# pre_amp.net
KiCad netlist of a schematic drawn in EAGLE
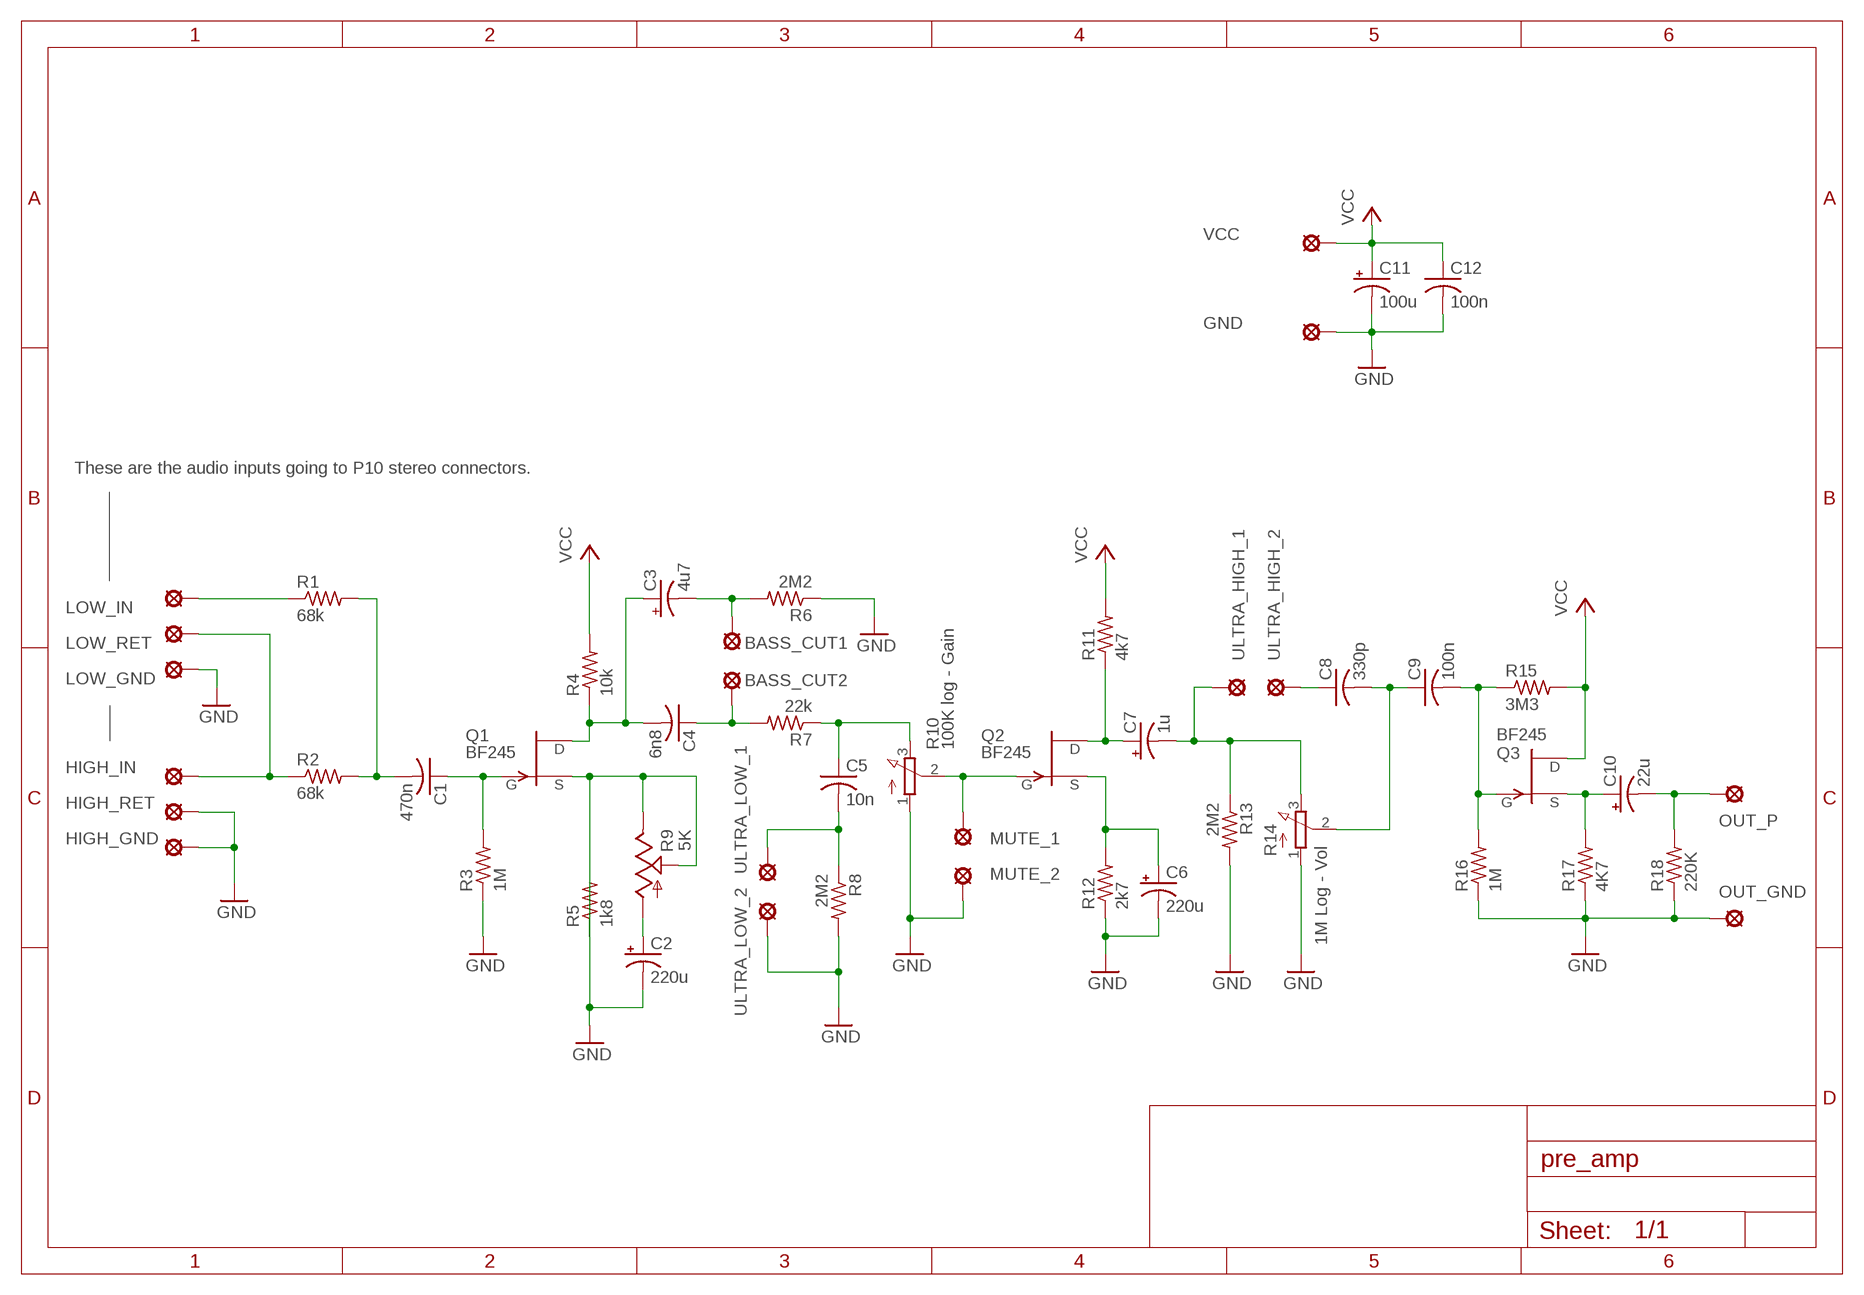
[diagram p0: schematic, sheet 1]

(export (version "E")
  (design (tool "Eeschema 10.0.6"))
  (components
    (comp (ref "BASS_CUT1")
      (value "MCS08")
      (footprint "eagle-import:MCS08")
      (libsource (lib "eagle-import") (part "MCS08"))
    )
    (comp (ref "BASS_CUT2")
      (value "MCS08")
      (footprint "eagle-import:MCS08")
      (libsource (lib "eagle-import") (part "MCS08"))
    )
    (comp (ref "C1")
      (value "470n")
      (footprint "eagle-import:C050-035X075")
      (libsource (lib "eagle-import") (part "resistor_C-US050-035X075"))
    )
    (comp (ref "C2")
      (value "220u")
      (footprint "eagle-import:E5-8,5")
      (libsource (lib "eagle-import") (part "resistor_CPOL-USE5-8.5"))
    )
    (comp (ref "C3")
      (value "4u7")
      (footprint "eagle-import:E2,5-6")
      (libsource (lib "eagle-import") (part "resistor_CPOL-USE2.5-6"))
    )
    (comp (ref "C4")
      (value "6n8")
      (footprint "eagle-import:C050-030X075")
      (libsource (lib "eagle-import") (part "C-US050-030X075"))
    )
    (comp (ref "C5")
      (value "10n")
      (footprint "eagle-import:C050-030X075")
      (libsource (lib "eagle-import") (part "C-US050-030X075"))
    )
    (comp (ref "C6")
      (value "220u")
      (footprint "eagle-import:E3,5-8")
      (libsource (lib "eagle-import") (part "resistor_CPOL-USE3.5-8"))
    )
    (comp (ref "C7")
      (value "1u")
      (footprint "eagle-import:E2,5-6")
      (libsource (lib "eagle-import") (part "CPOL-USE2.5-6"))
    )
    (comp (ref "C8")
      (value "330p")
      (footprint "eagle-import:C050-025X075")
      (libsource (lib "eagle-import") (part "C-US050-025X075"))
    )
    (comp (ref "C9")
      (value "100n")
      (footprint "eagle-import:C075-042X103")
      (libsource (lib "eagle-import") (part "C-US075-042X103"))
    )
    (comp (ref "C10")
      (value "22u")
      (footprint "eagle-import:E2-5")
      (libsource (lib "eagle-import") (part "CPOL-USE2-5"))
    )
    (comp (ref "C11")
      (value "100u")
      (footprint "eagle-import:E3,5-10")
      (libsource (lib "eagle-import") (part "CPOL-USE3.5-10"))
    )
    (comp (ref "C12")
      (value "100n")
      (footprint "eagle-import:C075-042X103")
      (libsource (lib "eagle-import") (part "C-US075-042X103"))
    )
    (comp (ref "GND")
      (value "MCS08")
      (footprint "eagle-import:MCS08")
      (libsource (lib "eagle-import") (part "MCS08"))
    )
    (comp (ref "HIGH_GND")
      (value "MCS08")
      (footprint "eagle-import:MCS08")
      (libsource (lib "eagle-import") (part "MCS08"))
    )
    (comp (ref "HIGH_IN")
      (value "MCS08")
      (footprint "eagle-import:MCS08")
      (libsource (lib "eagle-import") (part "MCS08"))
    )
    (comp (ref "HIGH_RET")
      (value "MCS08")
      (footprint "eagle-import:MCS08")
      (libsource (lib "eagle-import") (part "MCS08"))
    )
    (comp (ref "LOW_GND")
      (value "MCS08")
      (footprint "eagle-import:MCS08")
      (libsource (lib "eagle-import") (part "MCS08"))
    )
    (comp (ref "LOW_IN")
      (value "MCS08")
      (footprint "eagle-import:MCS08")
      (libsource (lib "eagle-import") (part "MCS08"))
    )
    (comp (ref "LOW_RET")
      (value "MCS08")
      (footprint "eagle-import:MCS08")
      (libsource (lib "eagle-import") (part "MCS08"))
    )
    (comp (ref "MUTE_1")
      (value "MCS08")
      (footprint "eagle-import:MCS08")
      (libsource (lib "eagle-import") (part "MCS08"))
    )
    (comp (ref "MUTE_2")
      (value "MCS08")
      (footprint "eagle-import:MCS08")
      (libsource (lib "eagle-import") (part "MCS08"))
    )
    (comp (ref "OUT_GND")
      (value "MCS08")
      (footprint "eagle-import:MCS08")
      (libsource (lib "eagle-import") (part "MCS08"))
    )
    (comp (ref "OUT_P")
      (value "MCS08")
      (footprint "eagle-import:MCS08")
      (libsource (lib "eagle-import") (part "MCS08"))
    )
    (comp (ref "Q1")
      (value "BF245")
      (footprint "eagle-import:TO92")
      (libsource (lib "eagle-import") (part "BF245"))
    )
    (comp (ref "Q2")
      (value "BF245")
      (footprint "eagle-import:TO92")
      (libsource (lib "eagle-import") (part "BF245"))
    )
    (comp (ref "Q3")
      (value "BF245")
      (footprint "eagle-import:TO92")
      (libsource (lib "eagle-import") (part "BF245"))
    )
    (comp (ref "R1")
      (value "68k")
      (footprint "eagle-import:0204_7")
      (libsource (lib "eagle-import") (part "R-US_0204/7"))
    )
    (comp (ref "R2")
      (value "68k")
      (footprint "eagle-import:0204_7")
      (libsource (lib "eagle-import") (part "R-US_0204/7"))
    )
    (comp (ref "R3")
      (value "1M")
      (footprint "eagle-import:0204_7")
      (libsource (lib "eagle-import") (part "R-US_0204/7"))
    )
    (comp (ref "R4")
      (value "10k")
      (footprint "eagle-import:0204_7")
      (libsource (lib "eagle-import") (part "R-US_0204/7"))
    )
    (comp (ref "R5")
      (value "1k8")
      (footprint "eagle-import:0207_10")
      (libsource (lib "eagle-import") (part "R-US_0207/10"))
    )
    (comp (ref "R6")
      (value "2M2")
      (footprint "eagle-import:0204_7")
      (libsource (lib "eagle-import") (part "R-US_0204/7"))
    )
    (comp (ref "R7")
      (value "22k")
      (footprint "eagle-import:0204_7")
      (libsource (lib "eagle-import") (part "R-US_0204/7"))
    )
    (comp (ref "R8")
      (value "2M2")
      (footprint "eagle-import:0204_7")
      (libsource (lib "eagle-import") (part "R-US_0204/7"))
    )
    (comp (ref "R9")
      (value "5K")
      (footprint "eagle-import:CA6V")
      (libsource (lib "eagle-import") (part "TRIM_US-CA6V"))
    )
    (comp (ref "R10")
      (value "100K log - Gain")
      (footprint "eagle-import:3RP_1610N")
      (libsource (lib "eagle-import") (part "3RP/1610N"))
    )
    (comp (ref "R11")
      (value "4k7")
      (footprint "eagle-import:0204_7")
      (libsource (lib "eagle-import") (part "R-US_0204/7"))
    )
    (comp (ref "R12")
      (value "2k7")
      (footprint "eagle-import:0204_7")
      (libsource (lib "eagle-import") (part "R-US_0204/7"))
    )
    (comp (ref "R13")
      (value "2M2")
      (footprint "eagle-import:0204_7")
      (libsource (lib "eagle-import") (part "R-US_0204/7"))
    )
    (comp (ref "R14")
      (value "1M Log - Vol")
      (footprint "eagle-import:3RP_1610N")
      (libsource (lib "eagle-import") (part "3RP/1610N"))
    )
    (comp (ref "R15")
      (value "3M3")
      (footprint "eagle-import:0204_7")
      (libsource (lib "eagle-import") (part "R-US_0204/7"))
    )
    (comp (ref "R16")
      (value "1M")
      (footprint "eagle-import:0204_7")
      (libsource (lib "eagle-import") (part "R-US_0204/7"))
    )
    (comp (ref "R17")
      (value "4K7")
      (footprint "eagle-import:0204_7")
      (libsource (lib "eagle-import") (part "R-US_0204/7"))
    )
    (comp (ref "R18")
      (value "220K")
      (footprint "eagle-import:0204_7")
      (libsource (lib "eagle-import") (part "R-US_0204/7"))
    )
    (comp (ref "ULTRA_HIGH_1")
      (value "MCS08")
      (footprint "eagle-import:MCS08")
      (libsource (lib "eagle-import") (part "MCS08"))
    )
    (comp (ref "ULTRA_HIGH_2")
      (value "MCS08")
      (footprint "eagle-import:MCS08")
      (libsource (lib "eagle-import") (part "MCS08"))
    )
    (comp (ref "ULTRA_LOW_1")
      (value "MCS08")
      (footprint "eagle-import:MCS08")
      (libsource (lib "eagle-import") (part "MCS08"))
    )
    (comp (ref "ULTRA_LOW_2")
      (value "MCS08")
      (footprint "eagle-import:MCS08")
      (libsource (lib "eagle-import") (part "MCS08"))
    )
    (comp (ref "VCC")
      (value "MCS08")
      (footprint "eagle-import:MCS08")
      (libsource (lib "eagle-import") (part "MCS08"))
    )
  )
  (nets
    (net (code "1") (name "GND") (class "Default")
      (node (ref "C11") (pin "-") (pinfunction "-_-") (pintype "passive"))
      (node (ref "C12") (pin "2") (pinfunction "2_2") (pintype "passive"))
      (node (ref "C2") (pin "-") (pinfunction "-_-") (pintype "passive"))
      (node (ref "C6") (pin "-") (pinfunction "-_-") (pintype "passive"))
      (node (ref "GND") (pin "MP") (pinfunction "MP_MP") (pintype "passive"))
      (node (ref "HIGH_GND") (pin "MP") (pinfunction "MP_MP") (pintype "passive"))
      (node (ref "HIGH_RET") (pin "MP") (pinfunction "MP_MP") (pintype "passive"))
      (node (ref "LOW_GND") (pin "MP") (pinfunction "MP_MP") (pintype "passive"))
      (node (ref "MUTE_2") (pin "MP") (pinfunction "MP_MP") (pintype "passive"))
      (node (ref "OUT_GND") (pin "MP") (pinfunction "MP_MP") (pintype "passive"))
      (node (ref "R10") (pin "1") (pinfunction "A_1") (pintype "passive"))
      (node (ref "R12") (pin "1") (pinfunction "1_1") (pintype "passive"))
      (node (ref "R13") (pin "2") (pinfunction "2_2") (pintype "passive"))
      (node (ref "R14") (pin "1") (pinfunction "A_1") (pintype "passive"))
      (node (ref "R16") (pin "1") (pinfunction "1_1") (pintype "passive"))
      (node (ref "R17") (pin "1") (pinfunction "1_1") (pintype "passive"))
      (node (ref "R18") (pin "1") (pinfunction "1_1") (pintype "passive"))
      (node (ref "R3") (pin "1") (pinfunction "1_1") (pintype "passive"))
      (node (ref "R5") (pin "2") (pinfunction "2_2") (pintype "passive"))
      (node (ref "R6") (pin "1") (pinfunction "1_1") (pintype "passive"))
      (node (ref "R8") (pin "2") (pinfunction "2_2") (pintype "passive"))
      (node (ref "ULTRA_LOW_2") (pin "MP") (pinfunction "MP_MP") (pintype "passive"))
    )
    (net (code "2") (name "Net-(BASS_CUT1-PadMP)") (class "Default")
      (node (ref "BASS_CUT1") (pin "MP") (pinfunction "MP_MP") (pintype "passive"))
      (node (ref "C3") (pin "-") (pinfunction "-_-") (pintype "passive"))
      (node (ref "R6") (pin "2") (pinfunction "2_2") (pintype "passive"))
    )
    (net (code "3") (name "Net-(BASS_CUT2-PadMP)") (class "Default")
      (node (ref "BASS_CUT2") (pin "MP") (pinfunction "MP_MP") (pintype "passive"))
      (node (ref "C4") (pin "1") (pinfunction "1_1") (pintype "passive"))
      (node (ref "R7") (pin "2") (pinfunction "2_2") (pintype "passive"))
    )
    (net (code "4") (name "Net-(C1-Pad2)") (class "Default")
      (node (ref "C1") (pin "2") (pinfunction "2_2") (pintype "passive"))
      (node (ref "R1") (pin "2") (pinfunction "2_2") (pintype "passive"))
      (node (ref "R2") (pin "2") (pinfunction "2_2") (pintype "passive"))
    )
    (net (code "5") (name "Net-(C2-Pad+)") (class "Default")
      (node (ref "C2") (pin "+") (pinfunction "+_+") (pintype "passive"))
      (node (ref "R9") (pin "A") (pinfunction "A_A") (pintype "passive"))
    )
    (net (code "6") (name "Net-(C5-Pad2)") (class "Default")
      (node (ref "C5") (pin "2") (pinfunction "2_2") (pintype "passive"))
      (node (ref "R8") (pin "1") (pinfunction "1_1") (pintype "passive"))
      (node (ref "ULTRA_LOW_1") (pin "MP") (pinfunction "MP_MP") (pintype "passive"))
    )
    (net (code "7") (name "Net-(C8-Pad1)") (class "Default")
      (node (ref "C8") (pin "1") (pinfunction "1_1") (pintype "passive"))
      (node (ref "ULTRA_HIGH_2") (pin "MP") (pinfunction "MP_MP") (pintype "passive"))
    )
    (net (code "8") (name "Net-(C10-Pad-)") (class "Default")
      (node (ref "C10") (pin "-") (pinfunction "-_-") (pintype "passive"))
      (node (ref "OUT_P") (pin "MP") (pinfunction "MP_MP") (pintype "passive"))
      (node (ref "R18") (pin "2") (pinfunction "2_2") (pintype "passive"))
    )
    (net (code "9") (name "Net-(HIGH_IN-PadMP)") (class "Default")
      (node (ref "HIGH_IN") (pin "MP") (pinfunction "MP_MP") (pintype "passive"))
      (node (ref "LOW_RET") (pin "MP") (pinfunction "MP_MP") (pintype "passive"))
      (node (ref "R2") (pin "1") (pinfunction "1_1") (pintype "passive"))
    )
    (net (code "10") (name "Net-(LOW_IN-PadMP)") (class "Default")
      (node (ref "LOW_IN") (pin "MP") (pinfunction "MP_MP") (pintype "passive"))
      (node (ref "R1") (pin "1") (pinfunction "1_1") (pintype "passive"))
    )
    (net (code "11") (name "Net-(Q1-D)") (class "Default")
      (node (ref "C3") (pin "+") (pinfunction "+_+") (pintype "passive"))
      (node (ref "C4") (pin "2") (pinfunction "2_2") (pintype "passive"))
      (node (ref "Q1") (pin "1") (pinfunction "D_1") (pintype "passive"))
      (node (ref "R4") (pin "1") (pinfunction "1_1") (pintype "passive"))
    )
    (net (code "12") (name "Net-(Q1-G)") (class "Default")
      (node (ref "C1") (pin "1") (pinfunction "1_1") (pintype "passive"))
      (node (ref "Q1") (pin "3") (pinfunction "G_3") (pintype "passive"))
      (node (ref "R3") (pin "2") (pinfunction "2_2") (pintype "passive"))
    )
    (net (code "13") (name "Net-(Q1-S)") (class "Default")
      (node (ref "Q1") (pin "2") (pinfunction "S_2") (pintype "passive"))
      (node (ref "R5") (pin "1") (pinfunction "1_1") (pintype "passive"))
      (node (ref "R9") (pin "E") (pinfunction "E_E") (pintype "passive"))
      (node (ref "R9") (pin "S") (pinfunction "S_S") (pintype "passive"))
    )
    (net (code "14") (name "Net-(Q2-D)") (class "Default")
      (node (ref "C7") (pin "+") (pinfunction "+_+") (pintype "passive"))
      (node (ref "Q2") (pin "1") (pinfunction "D_1") (pintype "passive"))
      (node (ref "R11") (pin "1") (pinfunction "1_1") (pintype "passive"))
    )
    (net (code "15") (name "Net-(Q2-G)") (class "Default")
      (node (ref "MUTE_1") (pin "MP") (pinfunction "MP_MP") (pintype "passive"))
      (node (ref "Q2") (pin "3") (pinfunction "G_3") (pintype "passive"))
      (node (ref "R10") (pin "2") (pinfunction "S_2") (pintype "passive"))
    )
    (net (code "16") (name "Net-(Q2-S)") (class "Default")
      (node (ref "C6") (pin "+") (pinfunction "+_+") (pintype "passive"))
      (node (ref "Q2") (pin "2") (pinfunction "S_2") (pintype "passive"))
      (node (ref "R12") (pin "2") (pinfunction "2_2") (pintype "passive"))
    )
    (net (code "17") (name "Net-(Q3-G)") (class "Default")
      (node (ref "C9") (pin "2") (pinfunction "2_2") (pintype "passive"))
      (node (ref "Q3") (pin "3") (pinfunction "G_3") (pintype "passive"))
      (node (ref "R15") (pin "1") (pinfunction "1_1") (pintype "passive"))
      (node (ref "R16") (pin "2") (pinfunction "2_2") (pintype "passive"))
    )
    (net (code "18") (name "Net-(Q3-S)") (class "Default")
      (node (ref "C10") (pin "+") (pinfunction "+_+") (pintype "passive"))
      (node (ref "Q3") (pin "2") (pinfunction "S_2") (pintype "passive"))
      (node (ref "R17") (pin "2") (pinfunction "2_2") (pintype "passive"))
    )
    (net (code "19") (name "Net-(R10-E)") (class "Default")
      (node (ref "C5") (pin "1") (pinfunction "1_1") (pintype "passive"))
      (node (ref "R10") (pin "3") (pinfunction "E_3") (pintype "passive"))
      (node (ref "R7") (pin "1") (pinfunction "1_1") (pintype "passive"))
    )
    (net (code "20") (name "Net-(R14-E)") (class "Default")
      (node (ref "C7") (pin "-") (pinfunction "-_-") (pintype "passive"))
      (node (ref "R13") (pin "1") (pinfunction "1_1") (pintype "passive"))
      (node (ref "R14") (pin "3") (pinfunction "E_3") (pintype "passive"))
      (node (ref "ULTRA_HIGH_1") (pin "MP") (pinfunction "MP_MP") (pintype "passive"))
    )
    (net (code "21") (name "Net-(R14-S)") (class "Default")
      (node (ref "C8") (pin "2") (pinfunction "2_2") (pintype "passive"))
      (node (ref "C9") (pin "1") (pinfunction "1_1") (pintype "passive"))
      (node (ref "R14") (pin "2") (pinfunction "S_2") (pintype "passive"))
    )
    (net (code "22") (name "VCC") (class "Default")
      (node (ref "C11") (pin "+") (pinfunction "+_+") (pintype "passive"))
      (node (ref "C12") (pin "1") (pinfunction "1_1") (pintype "passive"))
      (node (ref "Q3") (pin "1") (pinfunction "D_1") (pintype "passive"))
      (node (ref "R11") (pin "2") (pinfunction "2_2") (pintype "passive"))
      (node (ref "R15") (pin "2") (pinfunction "2_2") (pintype "passive"))
      (node (ref "R4") (pin "2") (pinfunction "2_2") (pintype "passive"))
      (node (ref "VCC") (pin "MP") (pinfunction "MP_MP") (pintype "passive"))
    )
  )
)
